# DM1092_Power_Supply.net
KiCad netlist of a schematic drawn in Altium Designer
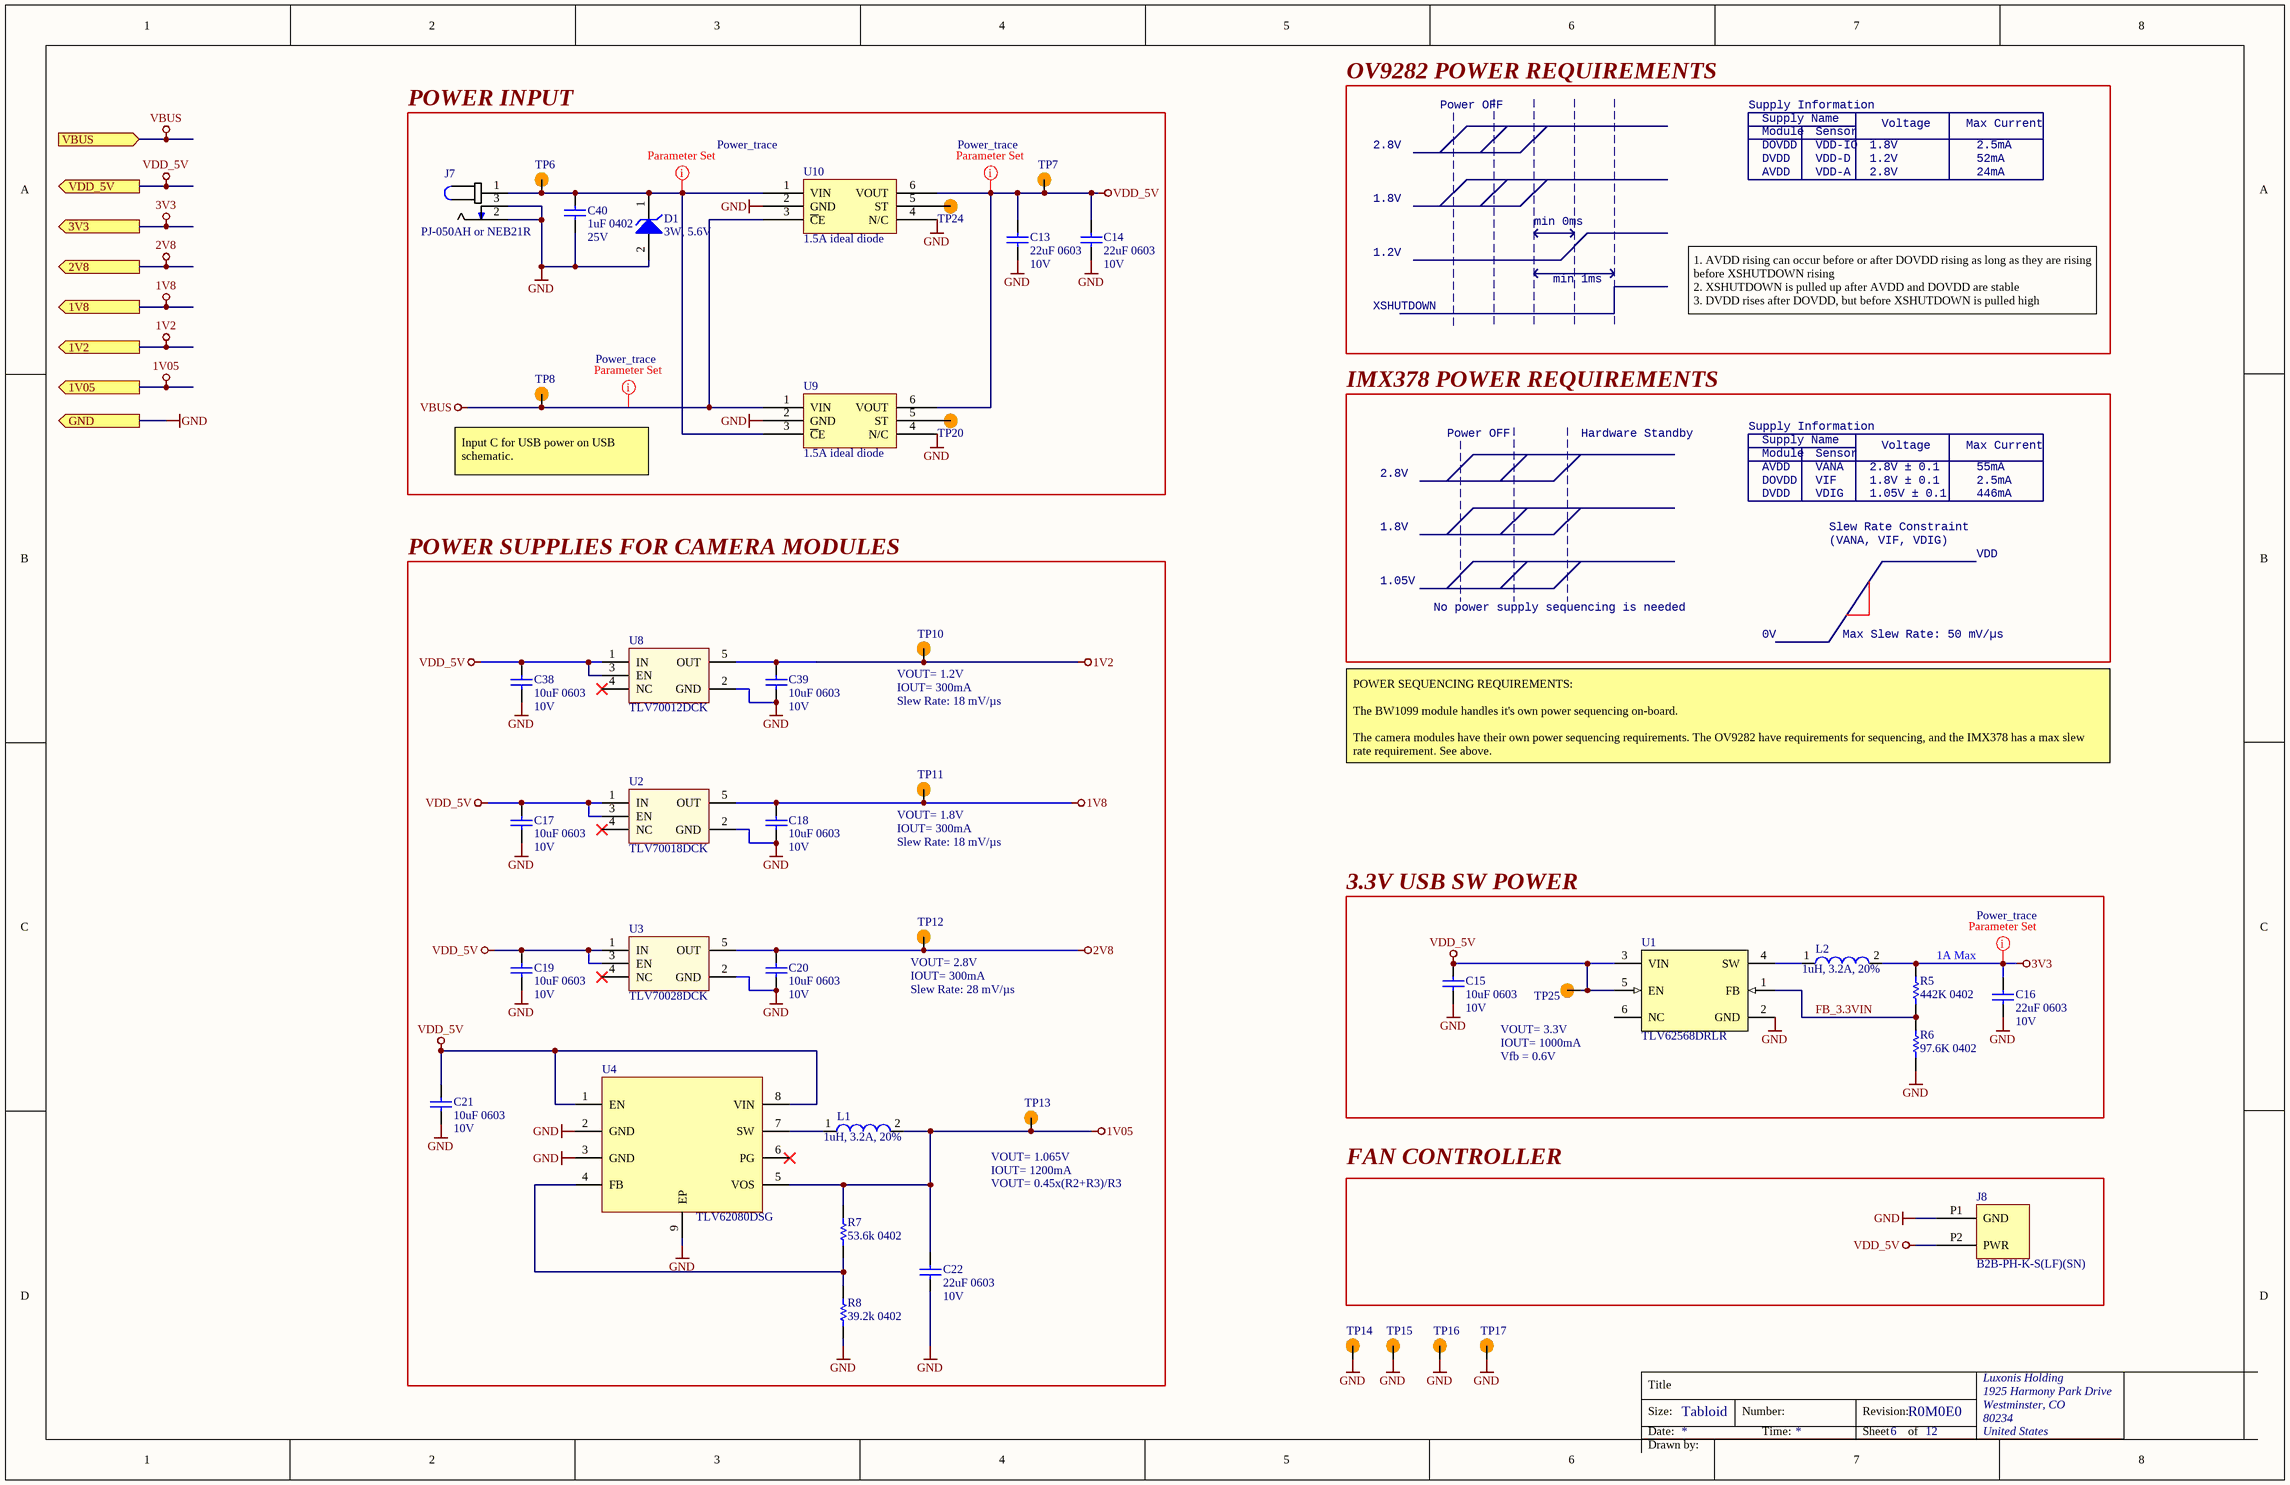
[diagram p0: DM1092_Power_Supply.SchDoc]

(export (version "E")
  (design (tool "Eeschema 10.0.6"))
  (components
    (comp (ref "C13")
      (value "22uF 0603")
      (footprint "CAP_Altium_Vault_Generic:CAPC0603(1608)100_L")
      (description "CAP CER 22UF 10V X5R 0603 20%")
      (fields (field (name "TOLERANCE") "20%") (field (name "VOLTAGE RATING") "10V"))
      (libsource (lib "LuxonisMaster") (part "GRM188R61A226ME15D"))
    )
    (comp (ref "C14")
      (value "22uF 0603")
      (footprint "CAP_Altium_Vault_Generic:CAPC0603(1608)100_L")
      (description "CAP CER 22UF 10V X5R 0603 20%")
      (fields (field (name "TOLERANCE") "20%") (field (name "VOLTAGE RATING") "10V"))
      (libsource (lib "LuxonisMaster") (part "GRM188R61A226ME15D"))
    )
    (comp (ref "C15")
      (value "10uF 0603")
      (footprint "CAP_Altium_Vault_Generic:CAPC0603(1608)100_L")
      (description "CAP CER 10UF 10V X5R 0603 20%")
      (fields (field (name "TOLERANCE") "20%") (field (name "VOLTAGE RATING") "10V"))
      (libsource (lib "LuxonisMaster") (part "GRM188R61A106ME69D"))
    )
    (comp (ref "C16")
      (value "22uF 0603")
      (footprint "CAP_Altium_Vault_Generic:CAPC0603(1608)100_N")
      (description "CAP CER 22UF 10V X5R 0603 20%")
      (fields (field (name "TOLERANCE") "20%") (field (name "VOLTAGE RATING") "10V"))
      (libsource (lib "LuxonisMaster") (part "GRM188R61A226ME15D"))
    )
    (comp (ref "C17")
      (value "10uF 0603")
      (footprint "CAP_Altium_Vault_Generic:CAPC0603(1608)100_L")
      (description "CAP CER 10UF 10V X5R 0603 20%")
      (fields (field (name "TOLERANCE") "20%") (field (name "VOLTAGE RATING") "10V"))
      (libsource (lib "LuxonisMaster") (part "GRM188R61A106ME69D"))
    )
    (comp (ref "C18")
      (value "10uF 0603")
      (footprint "CAP_Altium_Vault_Generic:CAPC0603(1608)100_L")
      (description "CAP CER 10UF 10V X5R 0603 20%")
      (fields (field (name "TOLERANCE") "20%") (field (name "VOLTAGE RATING") "10V"))
      (libsource (lib "LuxonisMaster") (part "GRM188R61A106ME69D"))
    )
    (comp (ref "C19")
      (value "10uF 0603")
      (footprint "CAP_Altium_Vault_Generic:CAPC0603(1608)100_L")
      (description "CAP CER 10UF 10V X5R 0603 20%")
      (fields (field (name "TOLERANCE") "20%") (field (name "VOLTAGE RATING") "10V"))
      (libsource (lib "LuxonisMaster") (part "GRM188R61A106ME69D"))
    )
    (comp (ref "C20")
      (value "10uF 0603")
      (footprint "CAP_Altium_Vault_Generic:CAPC0603(1608)100_L")
      (description "CAP CER 10UF 10V X5R 0603 20%")
      (fields (field (name "TOLERANCE") "20%") (field (name "VOLTAGE RATING") "10V"))
      (libsource (lib "LuxonisMaster") (part "GRM188R61A106ME69D"))
    )
    (comp (ref "C21")
      (value "10uF 0603")
      (footprint "CAP_Altium_Vault_Generic:CAPC0603(1608)100_L")
      (description "CAP CER 10UF 10V X5R 0603 20%")
      (fields (field (name "TOLERANCE") "20%") (field (name "VOLTAGE RATING") "10V"))
      (libsource (lib "LuxonisMaster") (part "GRM188R61A106ME69D"))
    )
    (comp (ref "C22")
      (value "22uF 0603")
      (footprint "CAP_Altium_Vault_Generic:CAPC0603(1608)100_L")
      (description "CAP CER 22UF 10V X5R 0603 20%")
      (fields (field (name "TOLERANCE") "20%") (field (name "VOLTAGE RATING") "10V"))
      (libsource (lib "LuxonisMaster") (part "GRM188R61A226ME15D"))
    )
    (comp (ref "C38")
      (value "10uF 0603")
      (footprint "CAP_Altium_Vault_Generic:CAPC0603(1608)100_L")
      (description "CAP CER 10UF 10V X5R 0603 20%")
      (fields (field (name "TOLERANCE") "20%") (field (name "VOLTAGE RATING") "10V"))
      (libsource (lib "LuxonisMaster") (part "GRM188R61A106ME69D"))
    )
    (comp (ref "C39")
      (value "10uF 0603")
      (footprint "CAP_Altium_Vault_Generic:CAPC0603(1608)100_L")
      (description "CAP CER 10UF 10V X5R 0603 20%")
      (fields (field (name "TOLERANCE") "20%") (field (name "VOLTAGE RATING") "10V"))
      (libsource (lib "LuxonisMaster") (part "GRM188R61A106ME69D"))
    )
    (comp (ref "C40")
      (value "1uF 0402")
      (footprint "CAP_Altium_Vault_Generic:CAPC0402(1005)70_L")
      (description "CAP CER 1UF 25V X5R 0402 10%")
      (fields
        (field (name "TOLERANCE") "10%")
        (field (name "VOLTAGE") "25V")
        (field (name "VOLTAGE RATING") "25V")
      )
      (libsource (lib "LuxonisMaster") (part "GRM155R61E105KA12D"))
    )
    (comp (ref "D1")
      (value "3W, 5.6V")
      (footprint "DM1092_R0M0E0:1SMB5919BT3G")
      (description "DIODE ZENER 5.6V 3W SMB")
      (fields (field (name "TOLERANCE") "5%"))
      (libsource (lib "DM1092_R0M0E0") (part "1SMB5919BT3G"))
    )
    (comp (ref "J7")
      (value "PJ-050AH or NEB21R")
      (footprint "LuxonisMaster:PJ-050AH/NEB21R_COMBO")
      (description "CONN POWER PIN 2 POS RA PTH Barrel jack 2.1mm x 5.5mm combo footprint")
      (libsource (lib "LuxonisMaster") (part "PJ-050AH/NEB21R_COMBO"))
    )
    (comp (ref "J8")
      (value "B2B-PH-K-S(LF)(SN)")
      (footprint "LuxonisMaster:B2B-PH-K-S(LF)(SN)")
      (description "CONN HEADER VERT 2POS 2MM")
      (fields (field (name "MANUFACTURER") "JST"))
      (libsource (lib "LuxonisMaster") (part "B2B-PH-K-S(LF)(SN)"))
    )
    (comp (ref "L1")
      (value "1uH, 3.2A, 20%")
      (footprint "LuxonisMaster:DFE252012P-1R0M=P2")
      (description "FIXED IND 1UH 3.2A 42 MOHM SMD")
      (fields
        (field (name "MANUFACTURER") "Murata")
        (field (name "MANUFACTURER PART NUMBER") "DFE252012P-1R0M=P2")
      )
      (libsource (lib "LuxonisMaster") (part "DFE252012P-1R0M=P2"))
    )
    (comp (ref "L2")
      (value "1uH, 3.2A, 20%")
      (footprint "LuxonisMaster:DFE252012P-1R0M=P2")
      (description "FIXED IND 1UH 3.2A 42 MOHM SMD")
      (fields
        (field (name "MANUFACTURER") "Murata")
        (field (name "MANUFACTURER PART NUMBER") "DFE252012P-1R0M=P2")
      )
      (libsource (lib "LuxonisMaster") (part "DFE252012P-1R0M=P2"))
    )
    (comp (ref "R5")
      (value "442K 0402")
      (footprint "RES_Altium_Vault_Generic:RESC0402(1005)_N")
      (description "RES SMD 442K OHM 1% 1/16W 0402")
      (fields (field (name "TOLERANCE") "1%"))
      (libsource (lib "BW1092_R0M0E0") (part "CRCW0402442KFKED"))
    )
    (comp (ref "R6")
      (value "97.6K 0402")
      (footprint "RES_Altium_Vault_Generic:RESC0402(1005)_N")
      (description "RES SMD 97.6K OHM 1% 1/16W 0402")
      (fields (field (name "TOLERANCE") "1%"))
      (libsource (lib "BW1092_R0M0E0") (part "CRCW040297K6FKED"))
    )
    (comp (ref "R7")
      (value "53.6k 0402")
      (footprint "RES_Altium_Vault_Generic:RESC0402(1005)_L")
      (description "RES SMD 53.6K OHM 1% 1/16W 0402")
      (fields (field (name "TOLERANCE") "1%"))
      (libsource (lib "LuxonisMaster") (part "CRCW040253K6FKED"))
    )
    (comp (ref "R8")
      (value "39.2k 0402")
      (footprint "RES_Altium_Vault_Generic:RESC0402(1005)_L")
      (description "RES SMD 39.2K OHM 1% 1/16W 0402")
      (fields (field (name "TOLERANCE") "1%"))
      (libsource (lib "LuxonisMaster") (part "CRCW040239K2FKED"))
    )
    (comp (ref "TP6")
      (value "TP100_200_NS")
      (footprint "LuxonisMaster:TP100_200_NS")
      (libsource (lib "LuxonisMaster") (part "TEST_POINT"))
    )
    (comp (ref "TP7")
      (value "TP100_200_NS")
      (footprint "LuxonisMaster:TP100_200_NS")
      (libsource (lib "LuxonisMaster") (part "TEST_POINT"))
    )
    (comp (ref "TP8")
      (value "TP100_200_NS")
      (footprint "LuxonisMaster:TP100_200_NS")
      (libsource (lib "LuxonisMaster") (part "TEST_POINT"))
    )
    (comp (ref "TP10")
      (value "TP100_200_NS")
      (footprint "LuxonisMaster:TP100_200_NS")
      (libsource (lib "LuxonisMaster") (part "TEST_POINT"))
    )
    (comp (ref "TP11")
      (value "TP100_200_NS")
      (footprint "LuxonisMaster:TP100_200_NS")
      (libsource (lib "LuxonisMaster") (part "TEST_POINT"))
    )
    (comp (ref "TP12")
      (value "TP100_200_NS")
      (footprint "LuxonisMaster:TP100_200_NS")
      (libsource (lib "LuxonisMaster") (part "TEST_POINT"))
    )
    (comp (ref "TP13")
      (value "TP100_200_NS")
      (footprint "LuxonisMaster:TP100_200_NS")
      (libsource (lib "LuxonisMaster") (part "TEST_POINT"))
    )
    (comp (ref "TP14")
      (value "TP100_200_NS")
      (footprint "LuxonisMaster:TP100_200_NS")
      (libsource (lib "LuxonisMaster") (part "TEST_POINT"))
    )
    (comp (ref "TP15")
      (value "TP100_200_NS")
      (footprint "LuxonisMaster:TP100_200_NS")
      (libsource (lib "LuxonisMaster") (part "TEST_POINT"))
    )
    (comp (ref "TP16")
      (value "TP100_200_NS")
      (footprint "LuxonisMaster:TP100_200_NS")
      (libsource (lib "LuxonisMaster") (part "TEST_POINT"))
    )
    (comp (ref "TP17")
      (value "TP100_200_NS")
      (footprint "LuxonisMaster:TP100_200_NS")
      (libsource (lib "LuxonisMaster") (part "TEST_POINT"))
    )
    (comp (ref "TP20")
      (value "TP100_200_NS")
      (footprint "LuxonisMaster:TP100_200_NS")
      (libsource (lib "LuxonisMaster") (part "TEST_POINT"))
    )
    (comp (ref "TP24")
      (value "TP100_200_NS")
      (footprint "LuxonisMaster:TP100_200_NS")
      (libsource (lib "LuxonisMaster") (part "TEST_POINT"))
    )
    (comp (ref "TP25")
      (value "TP100_200_NS")
      (footprint "LuxonisMaster:TP100_200_NS")
      (libsource (lib "LuxonisMaster") (part "TEST_POINT"))
    )
    (comp (ref "U1")
      (value "TLV62568DRLR")
      (footprint "BW1092_R0M0E0:TLV62568DRLR")
      (description "IC REG BUCK ADJ 1A SOT563-6")
      (libsource (lib "BW1092_R0M0E0") (part "TLV62568DRLR"))
    )
    (comp (ref "U2")
      (value "TLV70018DCK")
      (footprint "LuxonisMaster:TLV70018DCK")
      (description "IC REG LINEAR 1.8V 200MA SC70-5 Linear Voltage Regulator IC  1 Output  200mA SC-70-5")
      (libsource (lib "LuxonisMaster") (part "TLV70018DCK"))
    )
    (comp (ref "U3")
      (value "TLV70028DCK")
      (footprint "LuxonisMaster:TLV70028DCK")
      (description "IC REG LINEAR 2.8V 200MA SC70-5 Linear Voltage Regulator IC  1 Output  200mA SC-70-5")
      (libsource (lib "LuxonisMaster") (part "TLV70028DCK"))
    )
    (comp (ref "U4")
      (value "TLV62080DSG")
      (footprint "LuxonisMaster:TLV62080DSG")
      (description "IC REG BUCK ADJ 1.2A SYNC 8WSON")
      (libsource (lib "LuxonisMaster") (part "TLV62080DSG"))
    )
    (comp (ref "U8")
      (value "TLV70012DCK")
      (footprint "LuxonisMaster:TLV70012DCK")
      (description "IC REG LINEAR 1.2V 200MA SC70-5")
      (libsource (lib "LuxonisMaster") (part "TLV70012DCK"))
    )
    (comp (ref "U9")
      (value "1.5A ideal diode")
      (footprint "BW1098OBC_R2M0E2:LM66100DCKR")
      (description "IC OR CTRLR IDEAL DIODE SC70-6")
      (libsource (lib "BW1098OBC_R2M0E2") (part "LM66100DCKR"))
    )
    (comp (ref "U10")
      (value "1.5A ideal diode")
      (footprint "BW1098OBC_R2M0E2:LM66100DCKR")
      (description "IC OR CTRLR IDEAL DIODE SC70-6")
      (libsource (lib "BW1098OBC_R2M0E2") (part "LM66100DCKR"))
    )
  )
  (nets
    (net (code "1") (name "/FB_3.3VIN") (class "Default")
      (node (ref "R5") (pin "1") (pinfunction "1_1") (pintype "passive"))
      (node (ref "R6") (pin "2") (pinfunction "2_2") (pintype "passive"))
      (node (ref "U1") (pin "1") (pinfunction "FB_1") (pintype "input"))
    )
    (net (code "2") (name "1V2") (class "Default")
      (node (ref "C39") (pin "2") (pinfunction "2_2") (pintype "passive"))
      (node (ref "TP10") (pin "1") (pintype "passive"))
      (node (ref "U8") (pin "5") (pinfunction "OUT_5") (pintype "passive"))
    )
    (net (code "3") (name "1V05") (class "Default")
      (node (ref "C22") (pin "2") (pinfunction "2_2") (pintype "passive"))
      (node (ref "L1") (pin "2") (pinfunction "2_2") (pintype "passive"))
      (node (ref "R7") (pin "2") (pinfunction "2_2") (pintype "passive"))
      (node (ref "TP13") (pin "1") (pintype "passive"))
      (node (ref "U4") (pin "5") (pinfunction "VOS_5") (pintype "passive"))
    )
    (net (code "4") (name "1V8") (class "Default")
      (node (ref "C18") (pin "2") (pinfunction "2_2") (pintype "passive"))
      (node (ref "TP11") (pin "1") (pintype "passive"))
      (node (ref "U2") (pin "5") (pinfunction "OUT_5") (pintype "passive"))
    )
    (net (code "5") (name "2V8") (class "Default")
      (node (ref "C20") (pin "2") (pinfunction "2_2") (pintype "passive"))
      (node (ref "TP12") (pin "1") (pintype "passive"))
      (node (ref "U3") (pin "5") (pinfunction "OUT_5") (pintype "passive"))
    )
    (net (code "6") (name "3V3") (class "Default")
      (node (ref "C16") (pin "1") (pinfunction "1_1") (pintype "passive"))
      (node (ref "L2") (pin "2") (pinfunction "2_2") (pintype "passive"))
      (node (ref "R5") (pin "2") (pinfunction "2_2") (pintype "passive"))
    )
    (net (code "7") (name "GND") (class "Default")
      (node (ref "C13") (pin "1") (pinfunction "1_1") (pintype "passive"))
      (node (ref "C14") (pin "1") (pinfunction "1_1") (pintype "passive"))
      (node (ref "C15") (pin "1") (pinfunction "1_1") (pintype "passive"))
      (node (ref "C16") (pin "2") (pinfunction "2_2") (pintype "passive"))
      (node (ref "C17") (pin "1") (pinfunction "1_1") (pintype "passive"))
      (node (ref "C18") (pin "1") (pinfunction "1_1") (pintype "passive"))
      (node (ref "C19") (pin "1") (pinfunction "1_1") (pintype "passive"))
      (node (ref "C20") (pin "1") (pinfunction "1_1") (pintype "passive"))
      (node (ref "C21") (pin "1") (pinfunction "1_1") (pintype "passive"))
      (node (ref "C22") (pin "1") (pinfunction "1_1") (pintype "passive"))
      (node (ref "C38") (pin "1") (pinfunction "1_1") (pintype "passive"))
      (node (ref "C39") (pin "1") (pinfunction "1_1") (pintype "passive"))
      (node (ref "C40") (pin "1") (pinfunction "1_1") (pintype "passive"))
      (node (ref "D1") (pin "2") (pinfunction "A_2") (pintype "passive"))
      (node (ref "J7") (pin "2") (pinfunction "2_2") (pintype "passive"))
      (node (ref "J7") (pin "3") (pinfunction "3_3") (pintype "passive"))
      (node (ref "J8") (pin "P1") (pinfunction "GND_P1") (pintype "passive"))
      (node (ref "R6") (pin "1") (pinfunction "1_1") (pintype "passive"))
      (node (ref "R8") (pin "1") (pinfunction "1_1") (pintype "passive"))
      (node (ref "TP14") (pin "1") (pintype "passive"))
      (node (ref "TP15") (pin "1") (pintype "passive"))
      (node (ref "TP16") (pin "1") (pintype "passive"))
      (node (ref "TP17") (pin "1") (pintype "passive"))
      (node (ref "U1") (pin "2") (pinfunction "GND_2") (pintype "power_in"))
      (node (ref "U10") (pin "2") (pinfunction "GND_2") (pintype "passive"))
      (node (ref "U10") (pin "4") (pinfunction "N/C_4") (pintype "passive"))
      (node (ref "U2") (pin "2") (pinfunction "GND_2") (pintype "passive"))
      (node (ref "U3") (pin "2") (pinfunction "GND_2") (pintype "passive"))
      (node (ref "U4") (pin "2") (pinfunction "GND_2") (pintype "passive"))
      (node (ref "U4") (pin "3") (pinfunction "GND_3") (pintype "passive"))
      (node (ref "U4") (pin "9") (pinfunction "EP_9") (pintype "passive"))
      (node (ref "U8") (pin "2") (pinfunction "GND_2") (pintype "passive"))
      (node (ref "U9") (pin "2") (pinfunction "GND_2") (pintype "passive"))
      (node (ref "U9") (pin "4") (pinfunction "N/C_4") (pintype "passive"))
    )
    (net (code "8") (name "Net-(D1-K)") (class "Default")
      (node (ref "C40") (pin "2") (pinfunction "2_2") (pintype "passive"))
      (node (ref "D1") (pin "1") (pinfunction "K_1") (pintype "passive"))
      (node (ref "J7") (pin "1") (pinfunction "1_1") (pintype "passive"))
      (node (ref "TP6") (pin "1") (pintype "passive"))
      (node (ref "U10") (pin "1") (pinfunction "VIN_1") (pintype "passive"))
      (node (ref "U9") (pin "3") (pinfunction "~{C}E_3") (pintype "passive"))
    )
    (net (code "9") (name "Net-(U1-SW)") (class "Default")
      (node (ref "L2") (pin "1") (pinfunction "1_1") (pintype "passive"))
      (node (ref "U1") (pin "4") (pinfunction "SW_4") (pintype "power_in"))
    )
    (net (code "10") (name "Net-(U4-FB)") (class "Default")
      (node (ref "R7") (pin "1") (pinfunction "1_1") (pintype "passive"))
      (node (ref "R8") (pin "2") (pinfunction "2_2") (pintype "passive"))
      (node (ref "U4") (pin "4") (pinfunction "FB_4") (pintype "passive"))
    )
    (net (code "11") (name "Net-(U4-SW)") (class "Default")
      (node (ref "L1") (pin "1") (pinfunction "1_1") (pintype "passive"))
      (node (ref "U4") (pin "7") (pinfunction "SW_7") (pintype "passive"))
    )
    (net (code "12") (name "Net-(U9-ST)") (class "Default")
      (node (ref "TP20") (pin "1") (pintype "passive"))
      (node (ref "U9") (pin "5") (pinfunction "ST_5") (pintype "passive"))
    )
    (net (code "13") (name "Net-(U10-ST)") (class "Default")
      (node (ref "TP24") (pin "1") (pintype "passive"))
      (node (ref "U10") (pin "5") (pinfunction "ST_5") (pintype "passive"))
    )
    (net (code "14") (name "VBUS") (class "Default")
      (node (ref "TP8") (pin "1") (pintype "passive"))
      (node (ref "U10") (pin "3") (pinfunction "~{C}E_3") (pintype "passive"))
      (node (ref "U9") (pin "1") (pinfunction "VIN_1") (pintype "passive"))
    )
    (net (code "15") (name "VDD_5V") (class "Default")
      (node (ref "C13") (pin "2") (pinfunction "2_2") (pintype "passive"))
      (node (ref "C14") (pin "2") (pinfunction "2_2") (pintype "passive"))
      (node (ref "C15") (pin "2") (pinfunction "2_2") (pintype "passive"))
      (node (ref "C17") (pin "2") (pinfunction "2_2") (pintype "passive"))
      (node (ref "C19") (pin "2") (pinfunction "2_2") (pintype "passive"))
      (node (ref "C21") (pin "2") (pinfunction "2_2") (pintype "passive"))
      (node (ref "C38") (pin "2") (pinfunction "2_2") (pintype "passive"))
      (node (ref "J8") (pin "P2") (pinfunction "PWR_P2") (pintype "passive"))
      (node (ref "TP25") (pin "1") (pintype "passive"))
      (node (ref "TP7") (pin "1") (pintype "passive"))
      (node (ref "U1") (pin "3") (pinfunction "VIN_3") (pintype "power_in"))
      (node (ref "U1") (pin "5") (pinfunction "EN_5") (pintype "input"))
      (node (ref "U10") (pin "6") (pinfunction "VOUT_6") (pintype "passive"))
      (node (ref "U2") (pin "1") (pinfunction "IN_1") (pintype "passive"))
      (node (ref "U2") (pin "3") (pinfunction "EN_3") (pintype "passive"))
      (node (ref "U3") (pin "1") (pinfunction "IN_1") (pintype "passive"))
      (node (ref "U3") (pin "3") (pinfunction "EN_3") (pintype "passive"))
      (node (ref "U4") (pin "1") (pinfunction "EN_1") (pintype "passive"))
      (node (ref "U4") (pin "8") (pinfunction "VIN_8") (pintype "passive"))
      (node (ref "U8") (pin "1") (pinfunction "IN_1") (pintype "passive"))
      (node (ref "U8") (pin "3") (pinfunction "EN_3") (pintype "passive"))
      (node (ref "U9") (pin "6") (pinfunction "VOUT_6") (pintype "passive"))
    )
    (net (code "16") (name "unconnected-(U1-NC-Pad6)") (class "Default")
      (node (ref "U1") (pin "6") (pinfunction "NC_6") (pintype "passive"))
    )
    (net (code "17") (name "unconnected-(U2-NC-Pad4)") (class "Default")
      (node (ref "U2") (pin "4") (pinfunction "NC_4") (pintype "passive+no_connect"))
    )
    (net (code "18") (name "unconnected-(U3-NC-Pad4)") (class "Default")
      (node (ref "U3") (pin "4") (pinfunction "NC_4") (pintype "passive+no_connect"))
    )
    (net (code "19") (name "unconnected-(U4-PG-Pad6)") (class "Default")
      (node (ref "U4") (pin "6") (pinfunction "PG_6") (pintype "passive+no_connect"))
    )
    (net (code "20") (name "unconnected-(U8-NC-Pad4)") (class "Default")
      (node (ref "U8") (pin "4") (pinfunction "NC_4") (pintype "passive+no_connect"))
    )
  )
)
